# WiFi_Block_Controller_v2.net
KiCad netlist of a schematic drawn in EAGLE
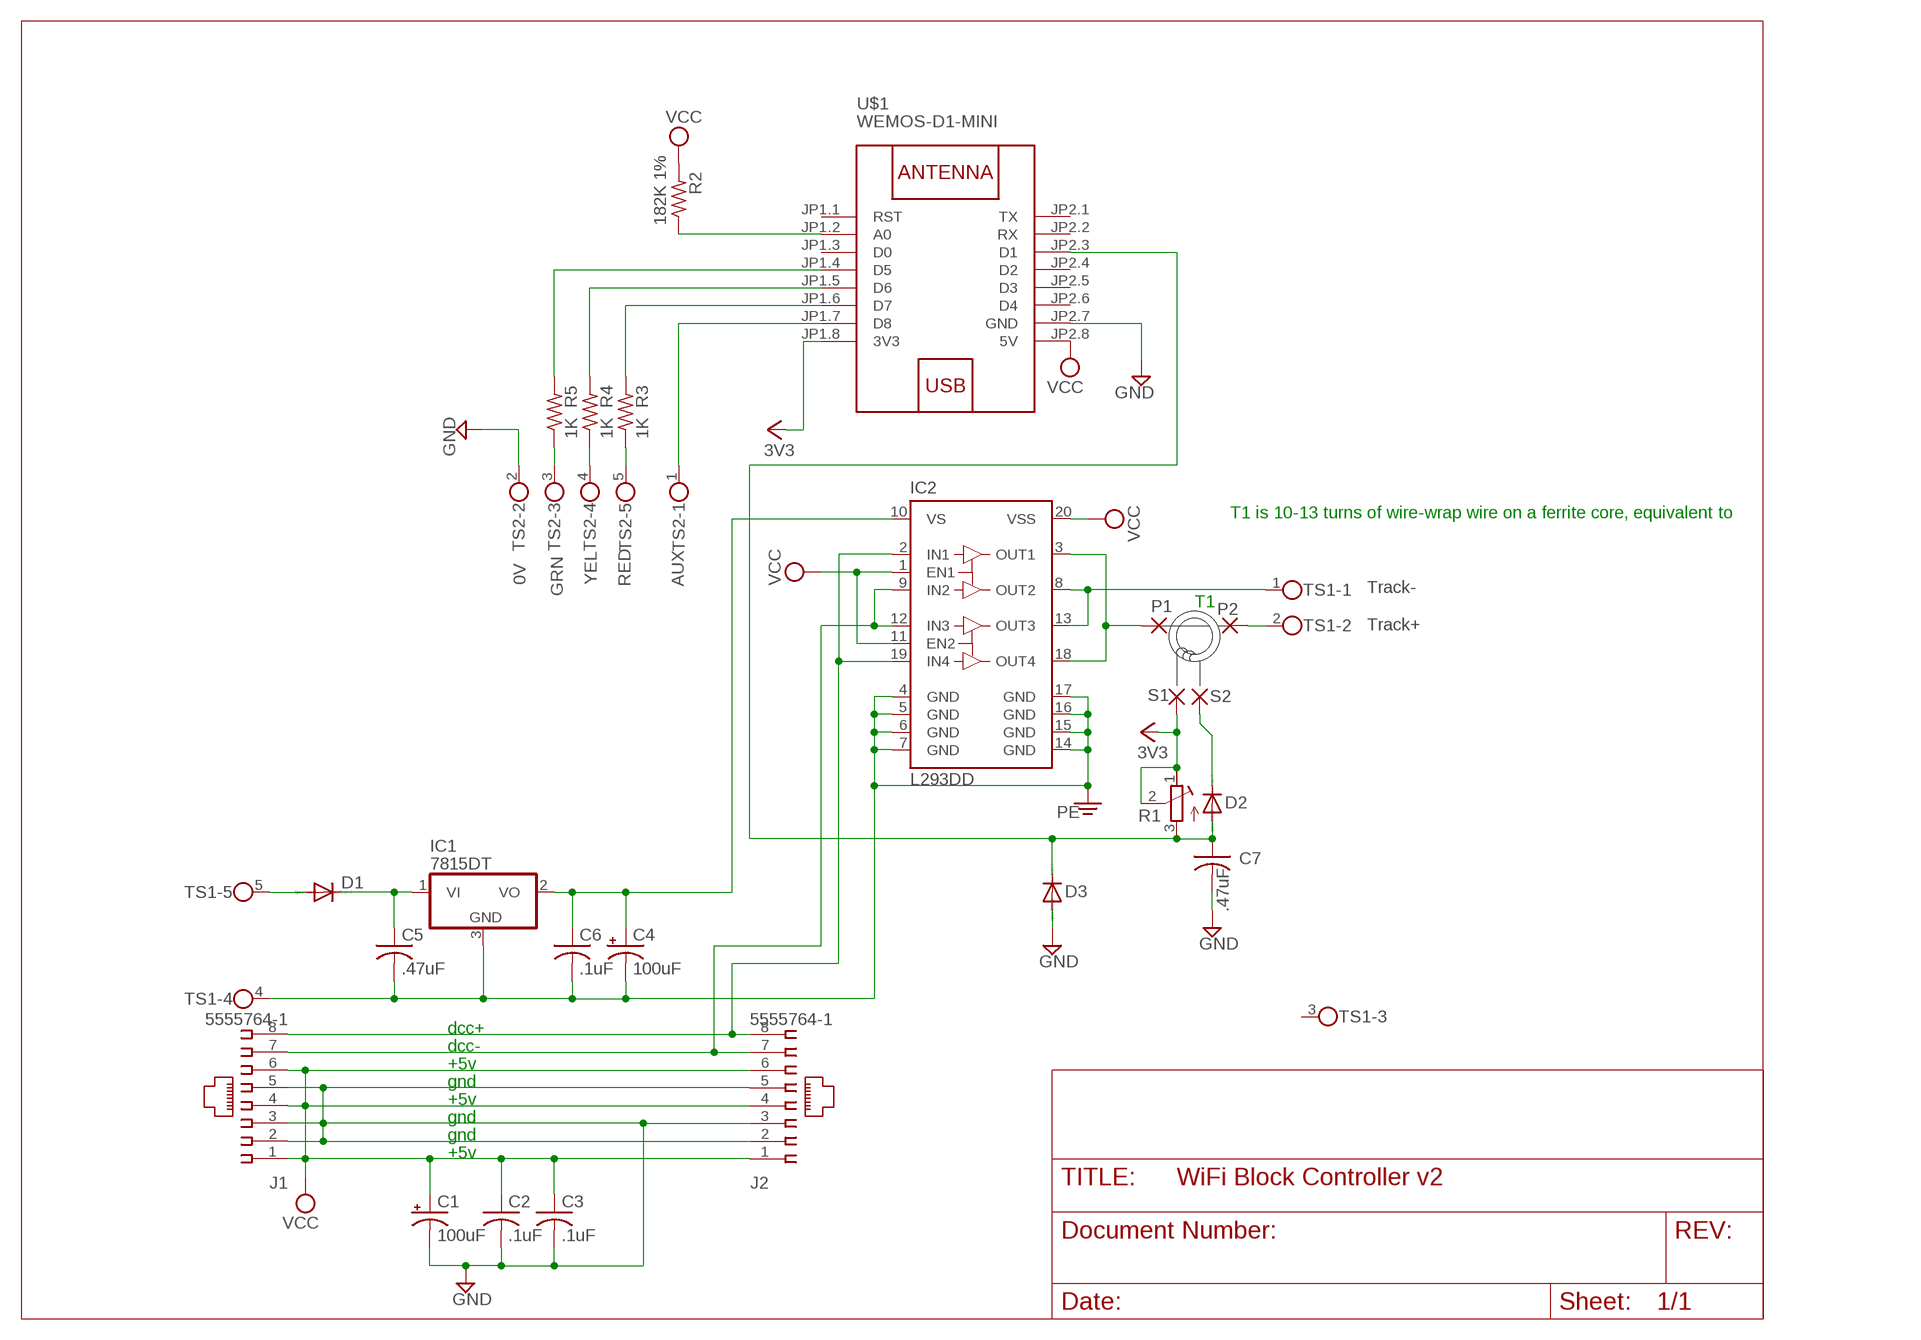
[diagram p0: schematic, sheet 1]

(export (version "E")
  (design (tool "Eeschema 10.0.6"))
  (components
    (comp (ref "C1")
      (value "100uF")
      (footprint "eagle-import:E3,5-8")
      (libsource (lib "eagle-import") (part "CPOL-USE3.5-8"))
    )
    (comp (ref "C2")
      (value ".1uF")
      (footprint "eagle-import:C1206")
      (libsource (lib "eagle-import") (part "C-USC1206"))
    )
    (comp (ref "C3")
      (value ".1uF")
      (footprint "eagle-import:C1206")
      (libsource (lib "eagle-import") (part "C-USC1206"))
    )
    (comp (ref "C4")
      (value "100uF")
      (footprint "eagle-import:E3,5-8")
      (libsource (lib "eagle-import") (part "CPOL-USE3.5-8"))
    )
    (comp (ref "C5")
      (value ".47uF")
      (footprint "eagle-import:C1206")
      (libsource (lib "eagle-import") (part "C-USC1206"))
    )
    (comp (ref "C6")
      (value ".1uF")
      (footprint "eagle-import:C1206")
      (libsource (lib "eagle-import") (part "C-USC1206"))
    )
    (comp (ref "C7")
      (value ".47uF")
      (footprint "eagle-import:C1206")
      (libsource (lib "eagle-import") (part "C-USC1206"))
    )
    (comp (ref "D1")
      (value "DIODE-DO-214AC")
      (footprint "eagle-import:DO-214AC")
      (libsource (lib "eagle-import") (part "DIODE-DO-214AC"))
    )
    (comp (ref "D2")
      (value "DIODE-SOD123")
      (footprint "eagle-import:SOD123")
      (libsource (lib "eagle-import") (part "DIODE-SOD123"))
    )
    (comp (ref "D3")
      (value "DIODE-SOD123")
      (footprint "eagle-import:SOD123")
      (libsource (lib "eagle-import") (part "DIODE-SOD123"))
    )
    (comp (ref "IC1")
      (value "7815DT")
      (footprint "eagle-import:TO252")
      (libsource (lib "eagle-import") (part "78DT18"))
    )
    (comp (ref "IC2")
      (value "L293DD")
      (footprint "eagle-import:SO20")
      (libsource (lib "eagle-import") (part "L293DD"))
    )
    (comp (ref "J1")
      (value "5555764-1")
      (footprint "eagle-import:520426-4")
      (libsource (lib "eagle-import") (part "520426-4"))
    )
    (comp (ref "J2")
      (value "5555764-1")
      (footprint "eagle-import:520426-4")
      (libsource (lib "eagle-import") (part "520426-4"))
    )
    (comp (ref "P1")
      (value "NA")
      (footprint "eagle-import:2,15_1,0")
      (libsource (lib "eagle-import") (part "2,15/1,0"))
    )
    (comp (ref "P2")
      (value "NA")
      (footprint "eagle-import:2,15_1,0")
      (libsource (lib "eagle-import") (part "2,15/1,0"))
    )
    (comp (ref "R1")
      (value "R-TRIMM3314G")
      (footprint "eagle-import:RTRIM3314G")
      (libsource (lib "eagle-import") (part "R-TRIMM3314G"))
    )
    (comp (ref "R2")
      (value "182K 1%")
      (footprint "eagle-import:M1206")
      (libsource (lib "eagle-import") (part "R-US_M1206"))
    )
    (comp (ref "R3")
      (value "1K")
      (footprint "eagle-import:M1206")
      (libsource (lib "eagle-import") (part "R-US_M1206"))
    )
    (comp (ref "R4")
      (value "1K")
      (footprint "eagle-import:M1206")
      (libsource (lib "eagle-import") (part "R-US_M1206"))
    )
    (comp (ref "R5")
      (value "1K")
      (footprint "eagle-import:M1206")
      (libsource (lib "eagle-import") (part "R-US_M1206"))
    )
    (comp (ref "S1")
      (value "2,15/1,0")
      (footprint "eagle-import:2,15_1,0")
      (libsource (lib "eagle-import") (part "2,15/1,0"))
    )
    (comp (ref "S2")
      (value "2,15/1,0")
      (footprint "eagle-import:2,15_1,0")
      (libsource (lib "eagle-import") (part "2,15/1,0"))
    )
    (comp (ref "TS1")
      (value "TERMBLK05")
      (footprint "eagle-import:05PB")
      (libsource (lib "eagle-import") (part "TERMBLK05"))
    )
    (comp (ref "TS2")
      (value "TERMBLK05")
      (footprint "eagle-import:05PB")
      (libsource (lib "eagle-import") (part "TERMBLK05"))
    )
    (comp (ref "U$1")
      (value "WEMOS-D1-MINI")
      (footprint "eagle-import:WEMOS-D1-MINI")
      (libsource (lib "eagle-import") (part "WEMOS-D1-MINI"))
    )
  )
  (nets
    (net (code "1") (name "3V3") (class "Default")
      (node (ref "R1") (pin "1") (pinfunction "E_1") (pintype "passive"))
      (node (ref "R1") (pin "2") (pinfunction "S_2") (pintype "passive"))
      (node (ref "S1") (pin "1") (pinfunction "P_1") (pintype "passive"))
      (node (ref "U$1") (pin "JP1.8") (pinfunction "3V3_JP1.8") (pintype "power_in"))
    )
    (net (code "2") (name "GND") (class "Default")
      (node (ref "C1") (pin "-") (pinfunction "-_-") (pintype "passive"))
      (node (ref "C2") (pin "2") (pinfunction "2_2") (pintype "passive"))
      (node (ref "C3") (pin "2") (pinfunction "2_2") (pintype "passive"))
      (node (ref "C7") (pin "2") (pinfunction "2_2") (pintype "passive"))
      (node (ref "D3") (pin "A") (pinfunction "A_A") (pintype "passive"))
      (node (ref "J1") (pin "2") (pinfunction "2_2") (pintype "passive"))
      (node (ref "J1") (pin "3") (pinfunction "3_3") (pintype "passive"))
      (node (ref "J1") (pin "5") (pinfunction "5_5") (pintype "passive"))
      (node (ref "J2") (pin "2") (pinfunction "2_2") (pintype "passive"))
      (node (ref "J2") (pin "3") (pinfunction "3_3") (pintype "passive"))
      (node (ref "J2") (pin "5") (pinfunction "5_5") (pintype "passive"))
      (node (ref "TS2") (pin "2") (pinfunction "1_2") (pintype "passive"))
      (node (ref "U$1") (pin "JP2.7") (pinfunction "GND_JP2.7") (pintype "power_in"))
    )
    (net (code "3") (name "Net-(IC1-VI)") (class "Default")
      (node (ref "C5") (pin "1") (pinfunction "1_1") (pintype "passive"))
      (node (ref "D1") (pin "C") (pinfunction "C_C") (pintype "passive"))
      (node (ref "IC1") (pin "1") (pinfunction "VI_1") (pintype "input"))
    )
    (net (code "4") (name "Net-(IC1-VO)") (class "Default")
      (node (ref "C4") (pin "+") (pinfunction "+_+") (pintype "passive"))
      (node (ref "C6") (pin "1") (pinfunction "1_1") (pintype "passive"))
      (node (ref "IC1") (pin "2") (pinfunction "VO_2") (pintype "passive"))
      (node (ref "IC2") (pin "10") (pinfunction "VS_10") (pintype "power_in"))
    )
    (net (code "5") (name "Net-(IC2-IN1)") (class "Default")
      (node (ref "IC2") (pin "19") (pinfunction "IN4_19") (pintype "input"))
      (node (ref "IC2") (pin "2") (pinfunction "IN1_2") (pintype "input"))
      (node (ref "J1") (pin "8") (pinfunction "8_8") (pintype "passive"))
      (node (ref "J2") (pin "8") (pinfunction "8_8") (pintype "passive"))
    )
    (net (code "6") (name "Net-(IC2-IN2)") (class "Default")
      (node (ref "IC2") (pin "12") (pinfunction "IN3_12") (pintype "input"))
      (node (ref "IC2") (pin "9") (pinfunction "IN2_9") (pintype "input"))
      (node (ref "J1") (pin "7") (pinfunction "7_7") (pintype "passive"))
      (node (ref "J2") (pin "7") (pinfunction "7_7") (pintype "passive"))
    )
    (net (code "7") (name "Net-(IC2-OUT1)") (class "Default")
      (node (ref "IC2") (pin "18") (pinfunction "OUT4_18") (pintype "output"))
      (node (ref "IC2") (pin "3") (pinfunction "OUT1_3") (pintype "output"))
      (node (ref "P1") (pin "1") (pinfunction "P_1") (pintype "passive"))
    )
    (net (code "8") (name "Net-(IC2-OUT2)") (class "Default")
      (node (ref "IC2") (pin "13") (pinfunction "OUT3_13") (pintype "output"))
      (node (ref "IC2") (pin "8") (pinfunction "OUT2_8") (pintype "output"))
      (node (ref "TS1") (pin "1") (pinfunction "1_1") (pintype "passive"))
    )
    (net (code "9") (name "Net-(P2-P)") (class "Default")
      (node (ref "P2") (pin "1") (pinfunction "P_1") (pintype "passive"))
      (node (ref "TS1") (pin "2") (pinfunction "1_2") (pintype "passive"))
    )
    (net (code "10") (name "Net-(R1-A)") (class "Default")
      (node (ref "C7") (pin "1") (pinfunction "1_1") (pintype "passive"))
      (node (ref "D2") (pin "A") (pinfunction "A_A") (pintype "passive"))
      (node (ref "D3") (pin "C") (pinfunction "C_C") (pintype "passive"))
      (node (ref "R1") (pin "3") (pinfunction "A_3") (pintype "passive"))
      (node (ref "U$1") (pin "JP2.3") (pinfunction "D1_JP2.3") (pintype "bidirectional"))
    )
    (net (code "11") (name "Net-(S2-P)") (class "Default")
      (node (ref "D2") (pin "C") (pinfunction "C_C") (pintype "passive"))
      (node (ref "S2") (pin "1") (pinfunction "P_1") (pintype "passive"))
    )
    (net (code "12") (name "Net-(TS1E-1)") (class "Default")
      (node (ref "D1") (pin "A") (pinfunction "A_A") (pintype "passive"))
      (node (ref "TS1") (pin "5") (pinfunction "1_5") (pintype "passive"))
    )
    (net (code "13") (name "Net-(TS2C-1)") (class "Default")
      (node (ref "R5") (pin "1") (pinfunction "1_1") (pintype "passive"))
      (node (ref "TS2") (pin "3") (pinfunction "1_3") (pintype "passive"))
    )
    (net (code "14") (name "Net-(TS2D-1)") (class "Default")
      (node (ref "R4") (pin "1") (pinfunction "1_1") (pintype "passive"))
      (node (ref "TS2") (pin "4") (pinfunction "1_4") (pintype "passive"))
    )
    (net (code "15") (name "Net-(TS2E-1)") (class "Default")
      (node (ref "R3") (pin "1") (pinfunction "1_1") (pintype "passive"))
      (node (ref "TS2") (pin "5") (pinfunction "1_5") (pintype "passive"))
    )
    (net (code "16") (name "Net-(U$1-A0)") (class "Default")
      (node (ref "R2") (pin "1") (pinfunction "1_1") (pintype "passive"))
      (node (ref "U$1") (pin "JP1.2") (pinfunction "A0_JP1.2") (pintype "bidirectional"))
    )
    (net (code "17") (name "Net-(U$1-D5)") (class "Default")
      (node (ref "R5") (pin "2") (pinfunction "2_2") (pintype "passive"))
      (node (ref "U$1") (pin "JP1.4") (pinfunction "D5_JP1.4") (pintype "bidirectional"))
    )
    (net (code "18") (name "Net-(U$1-D6)") (class "Default")
      (node (ref "R4") (pin "2") (pinfunction "2_2") (pintype "passive"))
      (node (ref "U$1") (pin "JP1.5") (pinfunction "D6_JP1.5") (pintype "bidirectional"))
    )
    (net (code "19") (name "Net-(U$1-D7)") (class "Default")
      (node (ref "R3") (pin "2") (pinfunction "2_2") (pintype "passive"))
      (node (ref "U$1") (pin "JP1.6") (pinfunction "D7_JP1.6") (pintype "bidirectional"))
    )
    (net (code "20") (name "Net-(U$1-D8)") (class "Default")
      (node (ref "TS2") (pin "1") (pinfunction "1_1") (pintype "passive"))
      (node (ref "U$1") (pin "JP1.7") (pinfunction "D8_JP1.7") (pintype "bidirectional"))
    )
    (net (code "21") (name "PE") (class "Default")
      (node (ref "C4") (pin "-") (pinfunction "-_-") (pintype "passive"))
      (node (ref "C5") (pin "2") (pinfunction "2_2") (pintype "passive"))
      (node (ref "C6") (pin "2") (pinfunction "2_2") (pintype "passive"))
      (node (ref "IC1") (pin "3") (pinfunction "GND_3") (pintype "passive"))
      (node (ref "IC2") (pin "14") (pinfunction "GND_14") (pintype "power_in"))
      (node (ref "IC2") (pin "15") (pinfunction "GND_15") (pintype "power_in"))
      (node (ref "IC2") (pin "16") (pinfunction "GND_16") (pintype "power_in"))
      (node (ref "IC2") (pin "17") (pinfunction "GND_17") (pintype "power_in"))
      (node (ref "IC2") (pin "4") (pinfunction "GND_4") (pintype "power_in"))
      (node (ref "IC2") (pin "5") (pinfunction "GND_5") (pintype "power_in"))
      (node (ref "IC2") (pin "6") (pinfunction "GND_6") (pintype "power_in"))
      (node (ref "IC2") (pin "7") (pinfunction "GND_7") (pintype "power_in"))
      (node (ref "TS1") (pin "4") (pinfunction "1_4") (pintype "passive"))
    )
    (net (code "22") (name "VCC") (class "Default")
      (node (ref "C1") (pin "+") (pinfunction "+_+") (pintype "passive"))
      (node (ref "C2") (pin "1") (pinfunction "1_1") (pintype "passive"))
      (node (ref "C3") (pin "1") (pinfunction "1_1") (pintype "passive"))
      (node (ref "IC2") (pin "1") (pinfunction "EN1_1") (pintype "input"))
      (node (ref "IC2") (pin "11") (pinfunction "EN2_11") (pintype "input"))
      (node (ref "IC2") (pin "20") (pinfunction "VSS_20") (pintype "power_in"))
      (node (ref "J1") (pin "1") (pinfunction "1_1") (pintype "passive"))
      (node (ref "J1") (pin "4") (pinfunction "4_4") (pintype "passive"))
      (node (ref "J1") (pin "6") (pinfunction "6_6") (pintype "passive"))
      (node (ref "J2") (pin "1") (pinfunction "1_1") (pintype "passive"))
      (node (ref "J2") (pin "4") (pinfunction "4_4") (pintype "passive"))
      (node (ref "J2") (pin "6") (pinfunction "6_6") (pintype "passive"))
      (node (ref "R2") (pin "2") (pinfunction "2_2") (pintype "passive"))
      (node (ref "U$1") (pin "JP2.8") (pinfunction "5V_JP2.8") (pintype "power_in"))
    )
    (net (code "23") (name "unconnected-(TS1C-1-Pad3)") (class "Default")
      (node (ref "TS1") (pin "3") (pinfunction "1_3") (pintype "passive"))
    )
    (net (code "24") (name "unconnected-(U$1-D0-PadJP1.3)") (class "Default")
      (node (ref "U$1") (pin "JP1.3") (pinfunction "D0_JP1.3") (pintype "bidirectional"))
    )
    (net (code "25") (name "unconnected-(U$1-D2-PadJP2.4)") (class "Default")
      (node (ref "U$1") (pin "JP2.4") (pinfunction "D2_JP2.4") (pintype "bidirectional"))
    )
    (net (code "26") (name "unconnected-(U$1-D3-PadJP2.5)") (class "Default")
      (node (ref "U$1") (pin "JP2.5") (pinfunction "D3_JP2.5") (pintype "bidirectional"))
    )
    (net (code "27") (name "unconnected-(U$1-D4-PadJP2.6)") (class "Default")
      (node (ref "U$1") (pin "JP2.6") (pinfunction "D4_JP2.6") (pintype "bidirectional"))
    )
    (net (code "28") (name "unconnected-(U$1-RST-PadJP1.1)") (class "Default")
      (node (ref "U$1") (pin "JP1.1") (pinfunction "RST_JP1.1") (pintype "bidirectional"))
    )
    (net (code "29") (name "unconnected-(U$1-RX-PadJP2.2)") (class "Default")
      (node (ref "U$1") (pin "JP2.2") (pinfunction "RX_JP2.2") (pintype "bidirectional"))
    )
    (net (code "30") (name "unconnected-(U$1-TX-PadJP2.1)") (class "Default")
      (node (ref "U$1") (pin "JP2.1") (pinfunction "TX_JP2.1") (pintype "bidirectional"))
    )
  )
)
